# jeet.net
KiCad netlist of a schematic drawn in EAGLE
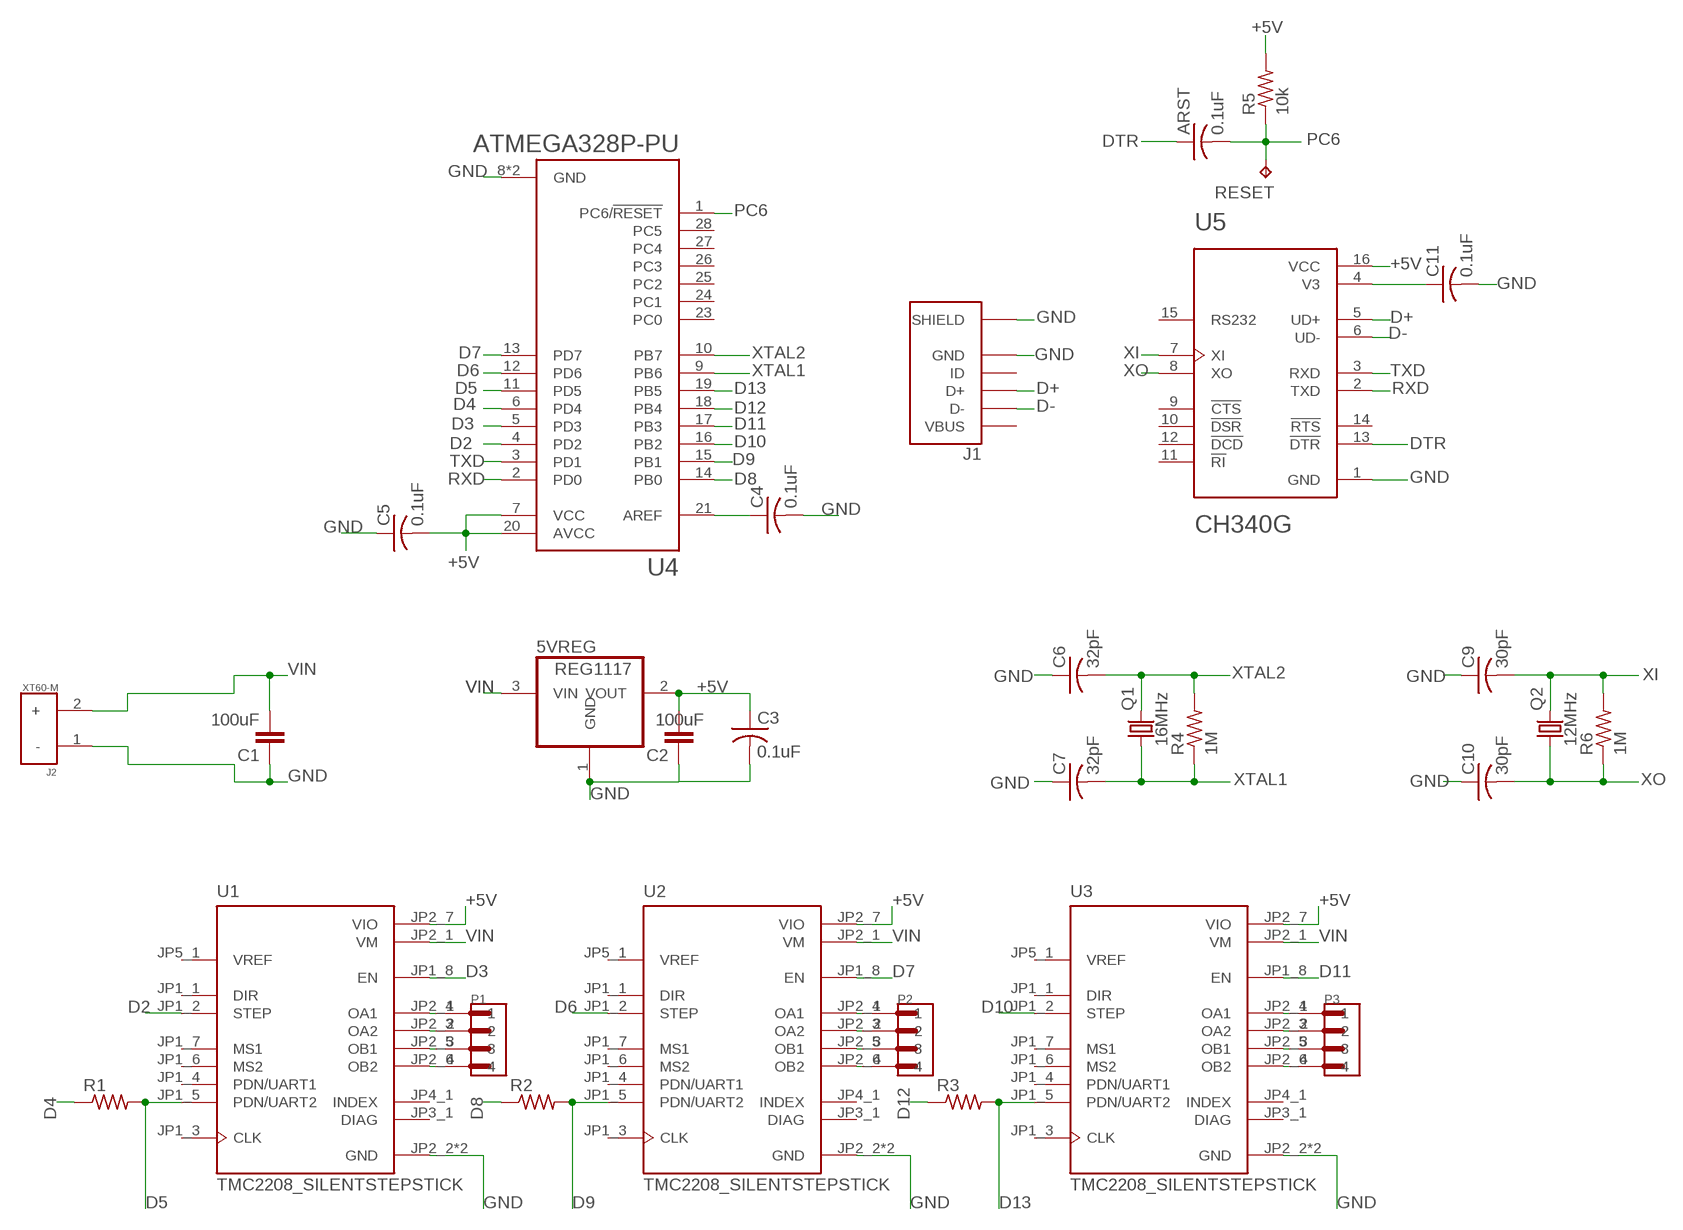
[diagram p0: schematic, sheet 1]

(export (version "E")
  (design (tool "Eeschema 10.0.6"))
  (components
    (comp (ref "5VREG")
      (value "REG1117")
      (footprint "eagle-import:SOT223")
      (libsource (lib "eagle-import") (part "REG1117"))
    )
    (comp (ref "ARST")
      (value "0.1uF")
      (footprint "eagle-import:C0805")
      (libsource (lib "eagle-import") (part "C-USC0805"))
    )
    (comp (ref "C1")
      (value "100uF")
      (footprint "eagle-import:C2.5-3")
      (libsource (lib "eagle-import") (part "C2,5-3"))
    )
    (comp (ref "C2")
      (value "100uF")
      (footprint "eagle-import:C2.5-3")
      (libsource (lib "eagle-import") (part "C2,5-3"))
    )
    (comp (ref "C3")
      (value "0.1uF")
      (footprint "eagle-import:C0805")
      (libsource (lib "eagle-import") (part "C-USC0805"))
    )
    (comp (ref "C4")
      (value "0.1uF")
      (footprint "eagle-import:C0805")
      (libsource (lib "eagle-import") (part "C-USC0805"))
    )
    (comp (ref "C5")
      (value "0.1uF")
      (footprint "eagle-import:C0805")
      (libsource (lib "eagle-import") (part "C-USC0805"))
    )
    (comp (ref "C6")
      (value "32pF")
      (footprint "eagle-import:C0805")
      (libsource (lib "eagle-import") (part "C-USC0805"))
    )
    (comp (ref "C7")
      (value "32pF")
      (footprint "eagle-import:C0805")
      (libsource (lib "eagle-import") (part "C-USC0805"))
    )
    (comp (ref "C9")
      (value "30pF")
      (footprint "eagle-import:C0805")
      (libsource (lib "eagle-import") (part "C-USC0805"))
    )
    (comp (ref "C10")
      (value "30pF")
      (footprint "eagle-import:C0805")
      (libsource (lib "eagle-import") (part "C-USC0805"))
    )
    (comp (ref "C11")
      (value "0.1uF")
      (footprint "eagle-import:C0805")
      (libsource (lib "eagle-import") (part "C-USC0805"))
    )
    (comp (ref "J1")
      (value "USB2066-05-RBHM-XX-STB-00-00-A_REVD")
      (footprint "eagle-import:GCT_USB2066-05-RBHM-XX-STB-00-00-A_REVD")
      (fields
        (field (name "MF") "Global Connector Technology")
        (field (name "MP") "USB2066-05-RBHM-15-STB-00-00-A")
      )
      (libsource (lib "eagle-import") (part "USB2066-05-RBHM-XX-STB-00-00-A_REVD"))
    )
    (comp (ref "J2")
      (value "XT60-M")
      (footprint "eagle-import:AMASS_XT60-M")
      (fields (field (name "MF") "AMASS"))
      (libsource (lib "eagle-import") (part "XT60-M"))
    )
    (comp (ref "P1")
      (value "S4B-XH-A(LF)(SN)")
      (footprint "eagle-import:JST_S4B-XH-A(LF)(SN)")
      (fields (field (name "MF") "JST Sales"))
      (libsource (lib "eagle-import") (part "S4B-XH-A(LF)(SN)"))
    )
    (comp (ref "P2")
      (value "S4B-XH-A(LF)(SN)")
      (footprint "eagle-import:JST_S4B-XH-A(LF)(SN)")
      (fields (field (name "MF") "JST Sales"))
      (libsource (lib "eagle-import") (part "S4B-XH-A(LF)(SN)"))
    )
    (comp (ref "P3")
      (value "S4B-XH-A(LF)(SN)")
      (footprint "eagle-import:JST_S4B-XH-A(LF)(SN)")
      (fields (field (name "MF") "JST Sales"))
      (libsource (lib "eagle-import") (part "S4B-XH-A(LF)(SN)"))
    )
    (comp (ref "Q1")
      (value "16MHz")
      (footprint "eagle-import:HC49_S")
      (libsource (lib "eagle-import") (part "CRYSTALHC49S"))
    )
    (comp (ref "Q2")
      (value "12MHz")
      (footprint "eagle-import:HC49_S")
      (libsource (lib "eagle-import") (part "CRYSTALHC49S"))
    )
    (comp (ref "R1")
      (value "R-US_R0805")
      (footprint "eagle-import:R0805")
      (libsource (lib "eagle-import") (part "R-US_R0805"))
    )
    (comp (ref "R2")
      (value "R-US_R0805")
      (footprint "eagle-import:R0805")
      (libsource (lib "eagle-import") (part "R-US_R0805"))
    )
    (comp (ref "R3")
      (value "R-US_R0805")
      (footprint "eagle-import:R0805")
      (libsource (lib "eagle-import") (part "R-US_R0805"))
    )
    (comp (ref "R4")
      (value "1M")
      (footprint "eagle-import:R0805")
      (libsource (lib "eagle-import") (part "R-US_R0805"))
    )
    (comp (ref "R5")
      (value "10k")
      (footprint "eagle-import:R0805")
      (libsource (lib "eagle-import") (part "R-US_R0805"))
    )
    (comp (ref "R6")
      (value "1M")
      (footprint "eagle-import:R0805")
      (libsource (lib "eagle-import") (part "R-US_R0805"))
    )
    (comp (ref "RESET")
      (value "TPB1,27")
      (footprint "eagle-import:B1,27")
      (libsource (lib "eagle-import") (part "TPB1,27"))
    )
    (comp (ref "U1")
      (value "TMC2208_SILENTSTEPSTICK")
      (footprint "eagle-import:MODULE_TMC2208_SILENTSTEPSTICK")
      (fields (field (name "MF") "Trinamic Motion") (field (name "MP") "TMC2208 SILENTSTEPSTICK"))
      (libsource (lib "eagle-import") (part "TMC2208_SILENTSTEPSTICK"))
    )
    (comp (ref "U2")
      (value "TMC2208_SILENTSTEPSTICK")
      (footprint "eagle-import:MODULE_TMC2208_SILENTSTEPSTICK")
      (fields (field (name "MF") "Trinamic Motion") (field (name "MP") "TMC2208 SILENTSTEPSTICK"))
      (libsource (lib "eagle-import") (part "TMC2208_SILENTSTEPSTICK"))
    )
    (comp (ref "U3")
      (value "TMC2208_SILENTSTEPSTICK")
      (footprint "eagle-import:MODULE_TMC2208_SILENTSTEPSTICK")
      (fields (field (name "MF") "Trinamic Motion") (field (name "MP") "TMC2208 SILENTSTEPSTICK"))
      (libsource (lib "eagle-import") (part "TMC2208_SILENTSTEPSTICK"))
    )
    (comp (ref "U4")
      (value "ATMEGA328P-PU")
      (footprint "eagle-import:DIP794W46P254L2967H457Q28B")
      (fields (field (name "MF") "Microchip Technology"))
      (libsource (lib "eagle-import") (part "ATMEGA328P-PU"))
    )
    (comp (ref "U5")
      (value "CH340G")
      (footprint "eagle-import:SOIC127P600X180-16N")
      (fields (field (name "MF") "WCH") (field (name "MP") "Ch340G"))
      (libsource (lib "eagle-import") (part "CH340G"))
    )
  )
  (nets
    (net (code "1") (name "/+5V") (class "Default")
      (node (ref "5VREG") (pin "2") (pinfunction "VOUT_2") (pintype "output"))
      (node (ref "C2") (pin "2") (pinfunction "2_2") (pintype "passive"))
      (node (ref "C3") (pin "1") (pinfunction "1_1") (pintype "passive"))
      (node (ref "C5") (pin "2") (pinfunction "2_2") (pintype "passive"))
      (node (ref "R5") (pin "2") (pinfunction "2_2") (pintype "passive"))
      (node (ref "U1") (pin "JP2_7") (pinfunction "VIO_JP2_7") (pintype "power_in"))
      (node (ref "U2") (pin "JP2_7") (pinfunction "VIO_JP2_7") (pintype "power_in"))
      (node (ref "U3") (pin "JP2_7") (pinfunction "VIO_JP2_7") (pintype "power_in"))
      (node (ref "U4") (pin "20") (pinfunction "AVCC_20") (pintype "power_in"))
      (node (ref "U4") (pin "7") (pinfunction "VCC_7") (pintype "power_in"))
      (node (ref "U5") (pin "16") (pinfunction "VCC_16") (pintype "power_in"))
    )
    (net (code "2") (name "/D+") (class "Default")
      (node (ref "J1") (pin "3") (pinfunction "D+_3") (pintype "bidirectional"))
      (node (ref "U5") (pin "5") (pinfunction "UD+_5") (pintype "bidirectional"))
    )
    (net (code "3") (name "/D-") (class "Default")
      (node (ref "J1") (pin "2") (pinfunction "D-_2") (pintype "bidirectional"))
      (node (ref "U5") (pin "6") (pinfunction "UD-_6") (pintype "bidirectional"))
    )
    (net (code "4") (name "/D2") (class "Default")
      (node (ref "U1") (pin "JP1_2") (pinfunction "STEP_JP1_2") (pintype "input"))
      (node (ref "U4") (pin "4") (pinfunction "PD2_4") (pintype "bidirectional"))
    )
    (net (code "5") (name "/D3") (class "Default")
      (node (ref "U1") (pin "JP1_8") (pinfunction "EN_JP1_8") (pintype "input"))
      (node (ref "U4") (pin "5") (pinfunction "PD3_5") (pintype "bidirectional"))
    )
    (net (code "6") (name "/D4") (class "Default")
      (node (ref "R1") (pin "1") (pinfunction "1_1") (pintype "passive"))
      (node (ref "U4") (pin "6") (pinfunction "PD4_6") (pintype "bidirectional"))
    )
    (net (code "7") (name "/D5") (class "Default")
      (node (ref "R1") (pin "2") (pinfunction "2_2") (pintype "passive"))
      (node (ref "U1") (pin "JP1_5") (pinfunction "PDN/UART2_JP1_5") (pintype "bidirectional"))
      (node (ref "U4") (pin "11") (pinfunction "PD5_11") (pintype "bidirectional"))
    )
    (net (code "8") (name "/D6") (class "Default")
      (node (ref "U2") (pin "JP1_2") (pinfunction "STEP_JP1_2") (pintype "input"))
      (node (ref "U4") (pin "12") (pinfunction "PD6_12") (pintype "bidirectional"))
    )
    (net (code "9") (name "/D7") (class "Default")
      (node (ref "U2") (pin "JP1_8") (pinfunction "EN_JP1_8") (pintype "input"))
      (node (ref "U4") (pin "13") (pinfunction "PD7_13") (pintype "bidirectional"))
    )
    (net (code "10") (name "/D8") (class "Default")
      (node (ref "R2") (pin "1") (pinfunction "1_1") (pintype "passive"))
      (node (ref "U4") (pin "14") (pinfunction "PB0_14") (pintype "bidirectional"))
    )
    (net (code "11") (name "/D9") (class "Default")
      (node (ref "R2") (pin "2") (pinfunction "2_2") (pintype "passive"))
      (node (ref "U2") (pin "JP1_5") (pinfunction "PDN/UART2_JP1_5") (pintype "bidirectional"))
      (node (ref "U4") (pin "15") (pinfunction "PB1_15") (pintype "bidirectional"))
    )
    (net (code "12") (name "/D10") (class "Default")
      (node (ref "U3") (pin "JP1_2") (pinfunction "STEP_JP1_2") (pintype "input"))
      (node (ref "U4") (pin "16") (pinfunction "PB2_16") (pintype "bidirectional"))
    )
    (net (code "13") (name "/D11") (class "Default")
      (node (ref "U3") (pin "JP1_8") (pinfunction "EN_JP1_8") (pintype "input"))
      (node (ref "U4") (pin "17") (pinfunction "PB3_17") (pintype "bidirectional"))
    )
    (net (code "14") (name "/D12") (class "Default")
      (node (ref "R3") (pin "1") (pinfunction "1_1") (pintype "passive"))
      (node (ref "U4") (pin "18") (pinfunction "PB4_18") (pintype "bidirectional"))
    )
    (net (code "15") (name "/D13") (class "Default")
      (node (ref "R3") (pin "2") (pinfunction "2_2") (pintype "passive"))
      (node (ref "U3") (pin "JP1_5") (pinfunction "PDN/UART2_JP1_5") (pintype "bidirectional"))
      (node (ref "U4") (pin "19") (pinfunction "PB5_19") (pintype "bidirectional"))
    )
    (net (code "16") (name "/DTR") (class "Default")
      (node (ref "ARST") (pin "1") (pinfunction "1_1") (pintype "passive"))
      (node (ref "U5") (pin "13") (pinfunction "~{DTR}_13") (pintype "output"))
    )
    (net (code "17") (name "/GND") (class "Default")
      (node (ref "5VREG") (pin "1") (pinfunction "GND_1") (pintype "power_in"))
      (node (ref "C1") (pin "1") (pinfunction "1_1") (pintype "passive"))
      (node (ref "C10") (pin "1") (pinfunction "1_1") (pintype "passive"))
      (node (ref "C11") (pin "2") (pinfunction "2_2") (pintype "passive"))
      (node (ref "C2") (pin "1") (pinfunction "1_1") (pintype "passive"))
      (node (ref "C3") (pin "2") (pinfunction "2_2") (pintype "passive"))
      (node (ref "C4") (pin "2") (pinfunction "2_2") (pintype "passive"))
      (node (ref "C5") (pin "1") (pinfunction "1_1") (pintype "passive"))
      (node (ref "C6") (pin "1") (pinfunction "1_1") (pintype "passive"))
      (node (ref "C7") (pin "1") (pinfunction "1_1") (pintype "passive"))
      (node (ref "C9") (pin "1") (pinfunction "1_1") (pintype "passive"))
      (node (ref "J1") (pin "5") (pinfunction "GND_5") (pintype "power_in"))
      (node (ref "J1") (pin "6") (pinfunction "SHIELD_6") (pintype "power_in"))
      (node (ref "J1") (pin "7") (pinfunction "SHIELD_7") (pintype "power_in"))
      (node (ref "J1") (pin "8") (pinfunction "SHIELD_8") (pintype "power_in"))
      (node (ref "J1") (pin "9") (pinfunction "SHIELD_9") (pintype "power_in"))
      (node (ref "J2") (pin "1") (pinfunction "-_1") (pintype "passive"))
      (node (ref "U1") (pin "JP2_2") (pinfunction "GND_JP2_2") (pintype "power_in"))
      (node (ref "U1") (pin "JP2_8") (pinfunction "GND_JP2_8") (pintype "power_in"))
      (node (ref "U2") (pin "JP2_2") (pinfunction "GND_JP2_2") (pintype "power_in"))
      (node (ref "U2") (pin "JP2_8") (pinfunction "GND_JP2_8") (pintype "power_in"))
      (node (ref "U3") (pin "JP2_2") (pinfunction "GND_JP2_2") (pintype "power_in"))
      (node (ref "U3") (pin "JP2_8") (pinfunction "GND_JP2_8") (pintype "power_in"))
      (node (ref "U4") (pin "22") (pinfunction "GND_22") (pintype "power_in"))
      (node (ref "U4") (pin "8") (pinfunction "GND_8") (pintype "power_in"))
      (node (ref "U5") (pin "1") (pinfunction "GND_1") (pintype "power_in"))
    )
    (net (code "18") (name "/PC6") (class "Default")
      (node (ref "ARST") (pin "2") (pinfunction "2_2") (pintype "passive"))
      (node (ref "R5") (pin "1") (pinfunction "1_1") (pintype "passive"))
      (node (ref "RESET") (pin "TP") (pinfunction "TP_TP") (pintype "input"))
      (node (ref "U4") (pin "1") (pinfunction "PC6/~{RESET}_1") (pintype "bidirectional"))
    )
    (net (code "19") (name "/RXD") (class "Default")
      (node (ref "U4") (pin "2") (pinfunction "PD0_2") (pintype "bidirectional"))
      (node (ref "U5") (pin "2") (pinfunction "TXD_2") (pintype "output"))
    )
    (net (code "20") (name "/TXD") (class "Default")
      (node (ref "U4") (pin "3") (pinfunction "PD1_3") (pintype "bidirectional"))
      (node (ref "U5") (pin "3") (pinfunction "RXD_3") (pintype "input"))
    )
    (net (code "21") (name "/VBUS") (class "Default")
      (node (ref "J1") (pin "1") (pinfunction "VBUS_1") (pintype "power_in"))
    )
    (net (code "22") (name "/VIN") (class "Default")
      (node (ref "5VREG") (pin "3") (pinfunction "VIN_3") (pintype "input"))
      (node (ref "C1") (pin "2") (pinfunction "2_2") (pintype "passive"))
      (node (ref "J2") (pin "2") (pinfunction "+_2") (pintype "passive"))
      (node (ref "U1") (pin "JP2_1") (pinfunction "VM_JP2_1") (pintype "power_in"))
      (node (ref "U2") (pin "JP2_1") (pinfunction "VM_JP2_1") (pintype "power_in"))
      (node (ref "U3") (pin "JP2_1") (pinfunction "VM_JP2_1") (pintype "power_in"))
    )
    (net (code "23") (name "/XI") (class "Default")
      (node (ref "C9") (pin "2") (pinfunction "2_2") (pintype "passive"))
      (node (ref "Q2") (pin "2") (pinfunction "2_2") (pintype "passive"))
      (node (ref "R6") (pin "2") (pinfunction "2_2") (pintype "passive"))
      (node (ref "U5") (pin "7") (pinfunction "XI_7") (pintype "input"))
    )
    (net (code "24") (name "/XO") (class "Default")
      (node (ref "C10") (pin "2") (pinfunction "2_2") (pintype "passive"))
      (node (ref "Q2") (pin "1") (pinfunction "1_1") (pintype "passive"))
      (node (ref "R6") (pin "1") (pinfunction "1_1") (pintype "passive"))
      (node (ref "U5") (pin "8") (pinfunction "XO_8") (pintype "output"))
    )
    (net (code "25") (name "/XTAL1") (class "Default")
      (node (ref "C7") (pin "2") (pinfunction "2_2") (pintype "passive"))
      (node (ref "Q1") (pin "1") (pinfunction "1_1") (pintype "passive"))
      (node (ref "R4") (pin "1") (pinfunction "1_1") (pintype "passive"))
      (node (ref "U4") (pin "9") (pinfunction "PB6_9") (pintype "bidirectional"))
    )
    (net (code "26") (name "/XTAL2") (class "Default")
      (node (ref "C6") (pin "2") (pinfunction "2_2") (pintype "passive"))
      (node (ref "Q1") (pin "2") (pinfunction "2_2") (pintype "passive"))
      (node (ref "R4") (pin "2") (pinfunction "2_2") (pintype "passive"))
      (node (ref "U4") (pin "10") (pinfunction "PB7_10") (pintype "bidirectional"))
    )
    (net (code "27") (name "Net-(U1-OA1)") (class "Default")
      (node (ref "P1") (pin "1") (pinfunction "1_1") (pintype "passive"))
      (node (ref "U1") (pin "JP2_4") (pinfunction "OA1_JP2_4") (pintype "passive"))
    )
    (net (code "28") (name "Net-(U1-OA2)") (class "Default")
      (node (ref "P1") (pin "2") (pinfunction "2_2") (pintype "passive"))
      (node (ref "U1") (pin "JP2_3") (pinfunction "OA2_JP2_3") (pintype "passive"))
    )
    (net (code "29") (name "Net-(U1-OB1)") (class "Default")
      (node (ref "P1") (pin "3") (pinfunction "3_3") (pintype "passive"))
      (node (ref "U1") (pin "JP2_5") (pinfunction "OB1_JP2_5") (pintype "passive"))
    )
    (net (code "30") (name "Net-(U1-OB2)") (class "Default")
      (node (ref "P1") (pin "4") (pinfunction "4_4") (pintype "passive"))
      (node (ref "U1") (pin "JP2_6") (pinfunction "OB2_JP2_6") (pintype "passive"))
    )
    (net (code "31") (name "Net-(U2-OA1)") (class "Default")
      (node (ref "P2") (pin "1") (pinfunction "1_1") (pintype "passive"))
      (node (ref "U2") (pin "JP2_4") (pinfunction "OA1_JP2_4") (pintype "passive"))
    )
    (net (code "32") (name "Net-(U2-OA2)") (class "Default")
      (node (ref "P2") (pin "2") (pinfunction "2_2") (pintype "passive"))
      (node (ref "U2") (pin "JP2_3") (pinfunction "OA2_JP2_3") (pintype "passive"))
    )
    (net (code "33") (name "Net-(U2-OB1)") (class "Default")
      (node (ref "P2") (pin "3") (pinfunction "3_3") (pintype "passive"))
      (node (ref "U2") (pin "JP2_5") (pinfunction "OB1_JP2_5") (pintype "passive"))
    )
    (net (code "34") (name "Net-(U2-OB2)") (class "Default")
      (node (ref "P2") (pin "4") (pinfunction "4_4") (pintype "passive"))
      (node (ref "U2") (pin "JP2_6") (pinfunction "OB2_JP2_6") (pintype "passive"))
    )
    (net (code "35") (name "Net-(U3-OA1)") (class "Default")
      (node (ref "P3") (pin "1") (pinfunction "1_1") (pintype "passive"))
      (node (ref "U3") (pin "JP2_4") (pinfunction "OA1_JP2_4") (pintype "passive"))
    )
    (net (code "36") (name "Net-(U3-OA2)") (class "Default")
      (node (ref "P3") (pin "2") (pinfunction "2_2") (pintype "passive"))
      (node (ref "U3") (pin "JP2_3") (pinfunction "OA2_JP2_3") (pintype "passive"))
    )
    (net (code "37") (name "Net-(U3-OB1)") (class "Default")
      (node (ref "P3") (pin "3") (pinfunction "3_3") (pintype "passive"))
      (node (ref "U3") (pin "JP2_5") (pinfunction "OB1_JP2_5") (pintype "passive"))
    )
    (net (code "38") (name "Net-(U3-OB2)") (class "Default")
      (node (ref "P3") (pin "4") (pinfunction "4_4") (pintype "passive"))
      (node (ref "U3") (pin "JP2_6") (pinfunction "OB2_JP2_6") (pintype "passive"))
    )
    (net (code "39") (name "Net-(U4-AREF)") (class "Default")
      (node (ref "C4") (pin "1") (pinfunction "1_1") (pintype "passive"))
      (node (ref "U4") (pin "21") (pinfunction "AREF_21") (pintype "input"))
    )
    (net (code "40") (name "Net-(U5-V3)") (class "Default")
      (node (ref "C11") (pin "1") (pinfunction "1_1") (pintype "passive"))
      (node (ref "U5") (pin "4") (pinfunction "V3_4") (pintype "power_in"))
    )
    (net (code "41") (name "unconnected-(J1-ID-Pad4)") (class "Default")
      (node (ref "J1") (pin "4") (pinfunction "ID_4") (pintype "bidirectional"))
    )
    (net (code "42") (name "unconnected-(U1-CLK-PadJP1_3)") (class "Default")
      (node (ref "U1") (pin "JP1_3") (pinfunction "CLK_JP1_3") (pintype "input"))
    )
    (net (code "43") (name "unconnected-(U1-DIAG-PadJP3_1)") (class "Default")
      (node (ref "U1") (pin "JP3_1") (pinfunction "DIAG_JP3_1") (pintype "output"))
    )
    (net (code "44") (name "unconnected-(U1-DIR-PadJP1_1)") (class "Default")
      (node (ref "U1") (pin "JP1_1") (pinfunction "DIR_JP1_1") (pintype "input"))
    )
    (net (code "45") (name "unconnected-(U1-INDEX-PadJP4_1)") (class "Default")
      (node (ref "U1") (pin "JP4_1") (pinfunction "INDEX_JP4_1") (pintype "output"))
    )
    (net (code "46") (name "unconnected-(U1-MS1-PadJP1_7)") (class "Default")
      (node (ref "U1") (pin "JP1_7") (pinfunction "MS1_JP1_7") (pintype "input"))
    )
    (net (code "47") (name "unconnected-(U1-MS2-PadJP1_6)") (class "Default")
      (node (ref "U1") (pin "JP1_6") (pinfunction "MS2_JP1_6") (pintype "input"))
    )
    (net (code "48") (name "unconnected-(U1-PDN{slash}UART1-PadJP1_4)") (class "Default")
      (node (ref "U1") (pin "JP1_4") (pinfunction "PDN/UART1_JP1_4") (pintype "bidirectional"))
    )
    (net (code "49") (name "unconnected-(U1-VREF-PadJP5_1)") (class "Default")
      (node (ref "U1") (pin "JP5_1") (pinfunction "VREF_JP5_1") (pintype "input"))
    )
    (net (code "50") (name "unconnected-(U2-CLK-PadJP1_3)") (class "Default")
      (node (ref "U2") (pin "JP1_3") (pinfunction "CLK_JP1_3") (pintype "input"))
    )
    (net (code "51") (name "unconnected-(U2-DIAG-PadJP3_1)") (class "Default")
      (node (ref "U2") (pin "JP3_1") (pinfunction "DIAG_JP3_1") (pintype "output"))
    )
    (net (code "52") (name "unconnected-(U2-DIR-PadJP1_1)") (class "Default")
      (node (ref "U2") (pin "JP1_1") (pinfunction "DIR_JP1_1") (pintype "input"))
    )
    (net (code "53") (name "unconnected-(U2-INDEX-PadJP4_1)") (class "Default")
      (node (ref "U2") (pin "JP4_1") (pinfunction "INDEX_JP4_1") (pintype "output"))
    )
    (net (code "54") (name "unconnected-(U2-MS1-PadJP1_7)") (class "Default")
      (node (ref "U2") (pin "JP1_7") (pinfunction "MS1_JP1_7") (pintype "input"))
    )
    (net (code "55") (name "unconnected-(U2-MS2-PadJP1_6)") (class "Default")
      (node (ref "U2") (pin "JP1_6") (pinfunction "MS2_JP1_6") (pintype "input"))
    )
    (net (code "56") (name "unconnected-(U2-PDN{slash}UART1-PadJP1_4)") (class "Default")
      (node (ref "U2") (pin "JP1_4") (pinfunction "PDN/UART1_JP1_4") (pintype "bidirectional"))
    )
    (net (code "57") (name "unconnected-(U2-VREF-PadJP5_1)") (class "Default")
      (node (ref "U2") (pin "JP5_1") (pinfunction "VREF_JP5_1") (pintype "input"))
    )
    (net (code "58") (name "unconnected-(U3-CLK-PadJP1_3)") (class "Default")
      (node (ref "U3") (pin "JP1_3") (pinfunction "CLK_JP1_3") (pintype "input"))
    )
    (net (code "59") (name "unconnected-(U3-DIAG-PadJP3_1)") (class "Default")
      (node (ref "U3") (pin "JP3_1") (pinfunction "DIAG_JP3_1") (pintype "output"))
    )
    (net (code "60") (name "unconnected-(U3-DIR-PadJP1_1)") (class "Default")
      (node (ref "U3") (pin "JP1_1") (pinfunction "DIR_JP1_1") (pintype "input"))
    )
    (net (code "61") (name "unconnected-(U3-INDEX-PadJP4_1)") (class "Default")
      (node (ref "U3") (pin "JP4_1") (pinfunction "INDEX_JP4_1") (pintype "output"))
    )
    (net (code "62") (name "unconnected-(U3-MS1-PadJP1_7)") (class "Default")
      (node (ref "U3") (pin "JP1_7") (pinfunction "MS1_JP1_7") (pintype "input"))
    )
    (net (code "63") (name "unconnected-(U3-MS2-PadJP1_6)") (class "Default")
      (node (ref "U3") (pin "JP1_6") (pinfunction "MS2_JP1_6") (pintype "input"))
    )
    (net (code "64") (name "unconnected-(U3-PDN{slash}UART1-PadJP1_4)") (class "Default")
      (node (ref "U3") (pin "JP1_4") (pinfunction "PDN/UART1_JP1_4") (pintype "bidirectional"))
    )
    (net (code "65") (name "unconnected-(U3-VREF-PadJP5_1)") (class "Default")
      (node (ref "U3") (pin "JP5_1") (pinfunction "VREF_JP5_1") (pintype "input"))
    )
    (net (code "66") (name "unconnected-(U4-PC0-Pad23)") (class "Default")
      (node (ref "U4") (pin "23") (pinfunction "PC0_23") (pintype "bidirectional"))
    )
    (net (code "67") (name "unconnected-(U4-PC1-Pad24)") (class "Default")
      (node (ref "U4") (pin "24") (pinfunction "PC1_24") (pintype "bidirectional"))
    )
    (net (code "68") (name "unconnected-(U4-PC2-Pad25)") (class "Default")
      (node (ref "U4") (pin "25") (pinfunction "PC2_25") (pintype "bidirectional"))
    )
    (net (code "69") (name "unconnected-(U4-PC3-Pad26)") (class "Default")
      (node (ref "U4") (pin "26") (pinfunction "PC3_26") (pintype "bidirectional"))
    )
    (net (code "70") (name "unconnected-(U4-PC4-Pad27)") (class "Default")
      (node (ref "U4") (pin "27") (pinfunction "PC4_27") (pintype "bidirectional"))
    )
    (net (code "71") (name "unconnected-(U4-PC5-Pad28)") (class "Default")
      (node (ref "U4") (pin "28") (pinfunction "PC5_28") (pintype "bidirectional"))
    )
    (net (code "72") (name "unconnected-(U5-RS232-Pad15)") (class "Default")
      (node (ref "U5") (pin "15") (pinfunction "RS232_15") (pintype "input"))
    )
    (net (code "73") (name "unconnected-(U5-~{CTS}-Pad9)") (class "Default")
      (node (ref "U5") (pin "9") (pinfunction "~{CTS}_9") (pintype "input"))
    )
    (net (code "74") (name "unconnected-(U5-~{DCD}-Pad12)") (class "Default")
      (node (ref "U5") (pin "12") (pinfunction "~{DCD}_12") (pintype "input"))
    )
    (net (code "75") (name "unconnected-(U5-~{DSR}-Pad10)") (class "Default")
      (node (ref "U5") (pin "10") (pinfunction "~{DSR}_10") (pintype "input"))
    )
    (net (code "76") (name "unconnected-(U5-~{RI}-Pad11)") (class "Default")
      (node (ref "U5") (pin "11") (pinfunction "~{RI}_11") (pintype "input"))
    )
    (net (code "77") (name "unconnected-(U5-~{RTS}-Pad14)") (class "Default")
      (node (ref "U5") (pin "14") (pinfunction "~{RTS}_14") (pintype "output"))
    )
  )
)
